# sb-sonata-usb.net
KiCad netlist of a schematic drawn in Altium Designer
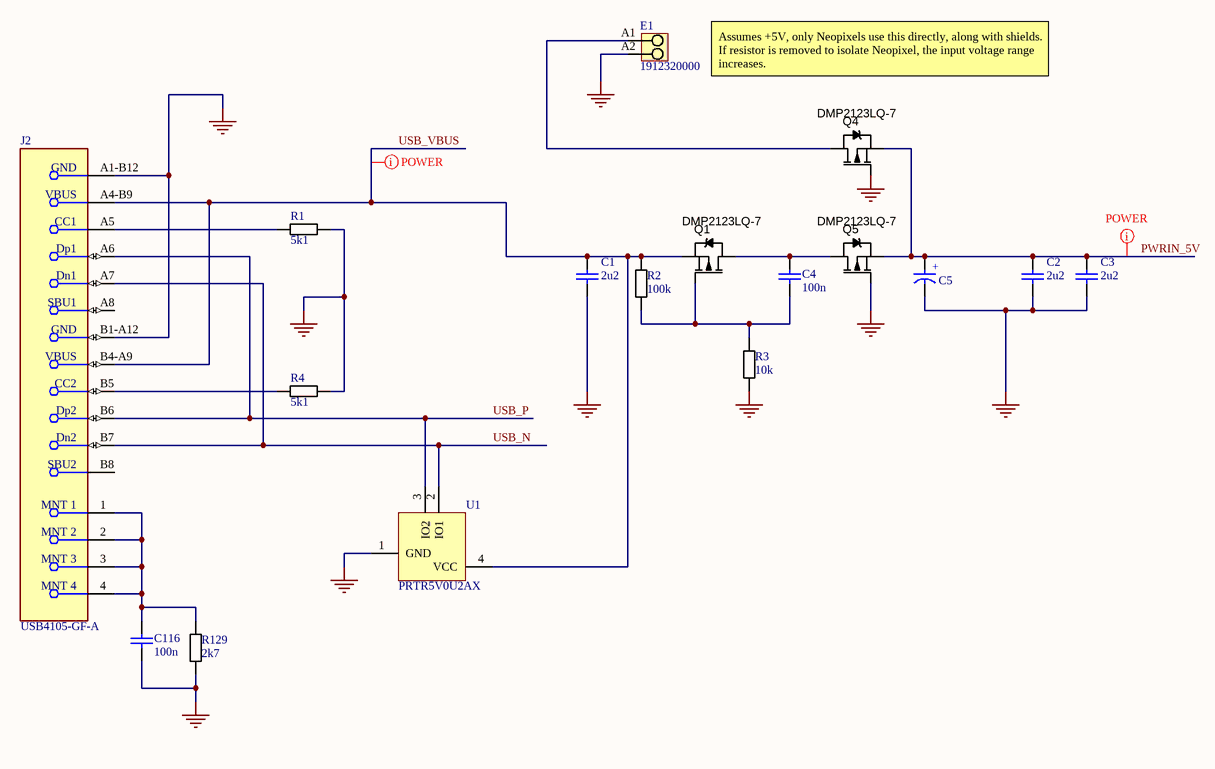
[diagram p0: sb-sonata-usb.SchDoc]

(export (version "E")
  (design (tool "Eeschema 10.0.6"))
  (components
    (comp (ref "C1")
      (value "2u2")
      (footprint "CAPC0603_M")
      (description "2u2, 0603")
      (fields (field (name "PART NUMBER") "CCHIP-2u2-0603"))
      (libsource (lib "NewAE_AltiumLib") (part "CAP"))
    )
    (comp (ref "C2")
      (value "2u2")
      (footprint "CAPC0603_M")
      (description "2u2, 0603")
      (fields (field (name "PART NUMBER") "CCHIP-2u2-0603"))
      (libsource (lib "NewAE_AltiumLib") (part "CAP"))
    )
    (comp (ref "C3")
      (value "2u2")
      (footprint "CAPC0603_M")
      (description "2u2, 0603")
      (fields (field (name "PART NUMBER") "CCHIP-2u2-0603"))
      (libsource (lib "NewAE_AltiumLib") (part "CAP"))
    )
    (comp (ref "C4")
      (value "100n")
      (footprint "CAPC0402_M")
      (description "100n, 0402")
      (fields (field (name "PART NUMBER") "CCHIP-100n-0402"))
      (libsource (lib "NewAE_AltiumLib") (part "CAP"))
    )
    (comp (ref "C5")
      (value "680uF")
      (footprint "Cap_16v_680uF")
      (description "Aluminum electrolytic 680uF, 8x16mm, radial")
      (fields (field (name "PART NUMBER") "Cap_16v_680uF"))
      (libsource (lib "NewAE_AltiumLib") (part "CAP_POL"))
    )
    (comp (ref "C116")
      (value "100n")
      (footprint "CAPC0402_M")
      (description "100n, 0402")
      (fields (field (name "PART NUMBER") "CCHIP-100n-0402"))
      (libsource (lib "NewAE_AltiumLib") (part "CAP"))
    )
    (comp (ref "E1")
      (value "1912320000")
      (footprint "PS_3_5_90_02")
      (description "OMNIMATE Signal - series PS")
      (fields (field (name "MANUFACTURER") "Weidmueller"))
      (libsource (lib "Altium Content Vault") (part "Terminal_02_1x02"))
    )
    (comp (ref "J2")
      (value "USB4105-GF-A")
      (footprint "FP-USB4105-GF-A-MFG")
      (description "CONN RCPT USB2.0 TYPEC 5A")
      (fields
        (field (name "MANUFACTURER") "GCT")
        (field (name "OCTOPART") "https://octopart.com/usb4105-gf-a-gct-106627878")
      )
      (libsource (lib "Altium Content Vault") (part "e7c17a616881a82b79941196b4bec10"))
    )
    (comp (ref "Q1")
      (value "DMP2123LQ-7")
      (footprint "SOT95P245X110-3M")
      (description "P-Channel, 3A, Logic Level")
      (libsource (lib "NewAE_AltiumLib") (part "MOSFET_P_GSD"))
    )
    (comp (ref "Q4")
      (value "DMP2123LQ-7")
      (footprint "SOT95P245X110-3M")
      (description "P-Channel, 3A, Logic Level")
      (libsource (lib "NewAE_AltiumLib") (part "MOSFET_P_GSD"))
    )
    (comp (ref "Q5")
      (value "DMP2123LQ-7")
      (footprint "SOT95P245X110-3M")
      (description "P-Channel, 3A, Logic Level")
      (libsource (lib "NewAE_AltiumLib") (part "MOSFET_P_GSD"))
    )
    (comp (ref "R1")
      (value "5k1")
      (footprint "RESC1608X55N")
      (description "5k1 res, 0603, 1%, 1/10W")
      (fields (field (name "PART NUMBER") "RCHIP-5K1-0603") (field (name "TOLERANCE") "1%"))
      (libsource (lib "") (part "RES-EU_1"))
    )
    (comp (ref "R2")
      (value "100k")
      (footprint "RESC1005X40N")
      (description "100k res, 0402, 1%, 1/16W")
      (fields (field (name "PART NUMBER") "RCHIP-100K-0402") (field (name "TOLERANCE") "1%"))
      (libsource (lib "NewAE_AltiumLib") (part "RES-EU"))
    )
    (comp (ref "R3")
      (value "10k")
      (footprint "RESC1005X40N")
      (description "10k res, 0402, 1%, 1/16W")
      (fields (field (name "PART NUMBER") "RCHIP-10K-0402") (field (name "TOLERANCE") "1%"))
      (libsource (lib "NewAE_AltiumLib") (part "RES-EU"))
    )
    (comp (ref "R4")
      (value "5k1")
      (footprint "RESC1608X55N")
      (description "5k1 res, 0603, 1%, 1/10W")
      (fields (field (name "PART NUMBER") "RCHIP-5K1-0603") (field (name "TOLERANCE") "1%"))
      (libsource (lib "") (part "RES-EU_1"))
    )
    (comp (ref "R129")
      (value "2k7")
      (footprint "RESC1005X40N")
      (description "2k7 res, 0402, 1%, 1/16W")
      (fields (field (name "PART NUMBER") "RCHIP-2K7-0402") (field (name "TOLERANCE") "1%"))
      (libsource (lib "NewAE_AltiumLib") (part "RES-EU"))
    )
    (comp (ref "U1")
      (value "PRTR5V0U2AX")
      (footprint "SOT143B")
      (description "USB 2.0 high-speed ESD")
      (libsource (lib "NewAE_AltiumLib") (part "PRTR5V0U2AX"))
    )
  )
  (nets
    (net (code "1") (name "/PWRIN_5V") (class "Default")
      (node (ref "C2") (pin "1") (pinfunction "1_1") (pintype "passive"))
      (node (ref "C3") (pin "1") (pinfunction "1_1") (pintype "passive"))
      (node (ref "C5") (pin "1") (pinfunction "1_1") (pintype "passive"))
      (node (ref "Q4") (pin "2") (pinfunction "S_2") (pintype "passive"))
      (node (ref "Q5") (pin "2") (pinfunction "S_2") (pintype "passive"))
    )
    (net (code "2") (name "/USB_N") (class "Default")
      (node (ref "J2") (pin "A7") (pinfunction "Dn1_A7") (pintype "bidirectional"))
      (node (ref "J2") (pin "B7") (pinfunction "Dn2_B7") (pintype "bidirectional"))
      (node (ref "U1") (pin "2") (pinfunction "IO1_2") (pintype "passive"))
    )
    (net (code "3") (name "/USB_P") (class "Default")
      (node (ref "J2") (pin "A6") (pinfunction "Dp1_A6") (pintype "bidirectional"))
      (node (ref "J2") (pin "B6") (pinfunction "Dp2_B6") (pintype "bidirectional"))
      (node (ref "U1") (pin "3") (pinfunction "IO2_3") (pintype "passive"))
    )
    (net (code "4") (name "/USB_VBUS") (class "Default")
      (node (ref "C1") (pin "1") (pinfunction "1_1") (pintype "passive"))
      (node (ref "J2") (pin "A4-B9") (pinfunction "VBUS_A4-B9") (pintype "power_in"))
      (node (ref "J2") (pin "B4-A9") (pinfunction "VBUS_B4-A9") (pintype "bidirectional"))
      (node (ref "Q1") (pin "2") (pinfunction "S_2") (pintype "passive"))
      (node (ref "R2") (pin "1") (pinfunction "1_1") (pintype "passive"))
      (node (ref "U1") (pin "4") (pinfunction "VCC_4") (pintype "power_in"))
    )
    (net (code "5") (name "GND") (class "Default")
      (node (ref "C1") (pin "2") (pinfunction "2_2") (pintype "passive"))
      (node (ref "C116") (pin "2") (pinfunction "2_2") (pintype "passive"))
      (node (ref "C2") (pin "2") (pinfunction "2_2") (pintype "passive"))
      (node (ref "C3") (pin "2") (pinfunction "2_2") (pintype "passive"))
      (node (ref "C5") (pin "2") (pinfunction "2_2") (pintype "passive"))
      (node (ref "E1") (pin "A2") (pinfunction "A2_A2") (pintype "passive"))
      (node (ref "J2") (pin "A1-B12") (pinfunction "GND_A1-B12") (pintype "power_in"))
      (node (ref "J2") (pin "B1-A12") (pinfunction "GND_B1-A12") (pintype "bidirectional"))
      (node (ref "Q4") (pin "1") (pinfunction "G_1") (pintype "passive"))
      (node (ref "Q5") (pin "1") (pinfunction "G_1") (pintype "passive"))
      (node (ref "R1") (pin "2") (pinfunction "2_2") (pintype "passive"))
      (node (ref "R129") (pin "2") (pinfunction "2_2") (pintype "passive"))
      (node (ref "R3") (pin "2") (pinfunction "2_2") (pintype "passive"))
      (node (ref "R4") (pin "2") (pinfunction "2_2") (pintype "passive"))
      (node (ref "U1") (pin "1") (pinfunction "GND_1") (pintype "power_in"))
    )
    (net (code "6") (name "Net-(J2-CC1)") (class "Default")
      (node (ref "J2") (pin "A5") (pinfunction "CC1_A5") (pintype "power_in"))
      (node (ref "R1") (pin "1") (pinfunction "1_1") (pintype "passive"))
    )
    (net (code "7") (name "Net-(J2-CC2)") (class "Default")
      (node (ref "J2") (pin "B5") (pinfunction "CC2_B5") (pintype "bidirectional"))
      (node (ref "R4") (pin "1") (pinfunction "1_1") (pintype "passive"))
    )
    (net (code "8") (name "Net-(J2-MNT_1)") (class "Default")
      (node (ref "C116") (pin "1") (pinfunction "1_1") (pintype "passive"))
      (node (ref "J2") (pin "1") (pinfunction "MNT_1_1") (pintype "power_in"))
      (node (ref "J2") (pin "2") (pinfunction "MNT_2_2") (pintype "power_in"))
      (node (ref "J2") (pin "3") (pinfunction "MNT_3_3") (pintype "power_in"))
      (node (ref "J2") (pin "4") (pinfunction "MNT_4_4") (pintype "power_in"))
      (node (ref "R129") (pin "1") (pinfunction "1_1") (pintype "passive"))
    )
    (net (code "9") (name "Net-(Q1-D)") (class "Default")
      (node (ref "C4") (pin "1") (pinfunction "1_1") (pintype "passive"))
      (node (ref "Q1") (pin "3") (pinfunction "D_3") (pintype "passive"))
      (node (ref "Q5") (pin "3") (pinfunction "D_3") (pintype "passive"))
    )
    (net (code "10") (name "Net-(Q1-G)") (class "Default")
      (node (ref "C4") (pin "2") (pinfunction "2_2") (pintype "passive"))
      (node (ref "Q1") (pin "1") (pinfunction "G_1") (pintype "passive"))
      (node (ref "R2") (pin "2") (pinfunction "2_2") (pintype "passive"))
      (node (ref "R3") (pin "1") (pinfunction "1_1") (pintype "passive"))
    )
    (net (code "11") (name "Net-(Q4-D)") (class "Default")
      (node (ref "E1") (pin "A1") (pinfunction "A1_A1") (pintype "passive"))
      (node (ref "Q4") (pin "3") (pinfunction "D_3") (pintype "passive"))
    )
    (net (code "12") (name "unconnected-(J2-SBU1-PadA8)") (class "Default")
      (node (ref "J2") (pin "A8") (pinfunction "SBU1_A8") (pintype "bidirectional"))
    )
    (net (code "13") (name "unconnected-(J2-SBU2-PadB8)") (class "Default")
      (node (ref "J2") (pin "B8") (pinfunction "SBU2_B8") (pintype "power_in"))
    )
  )
)
